# MIC_Speaker.net
KiCad netlist of a schematic drawn in Altium Designer
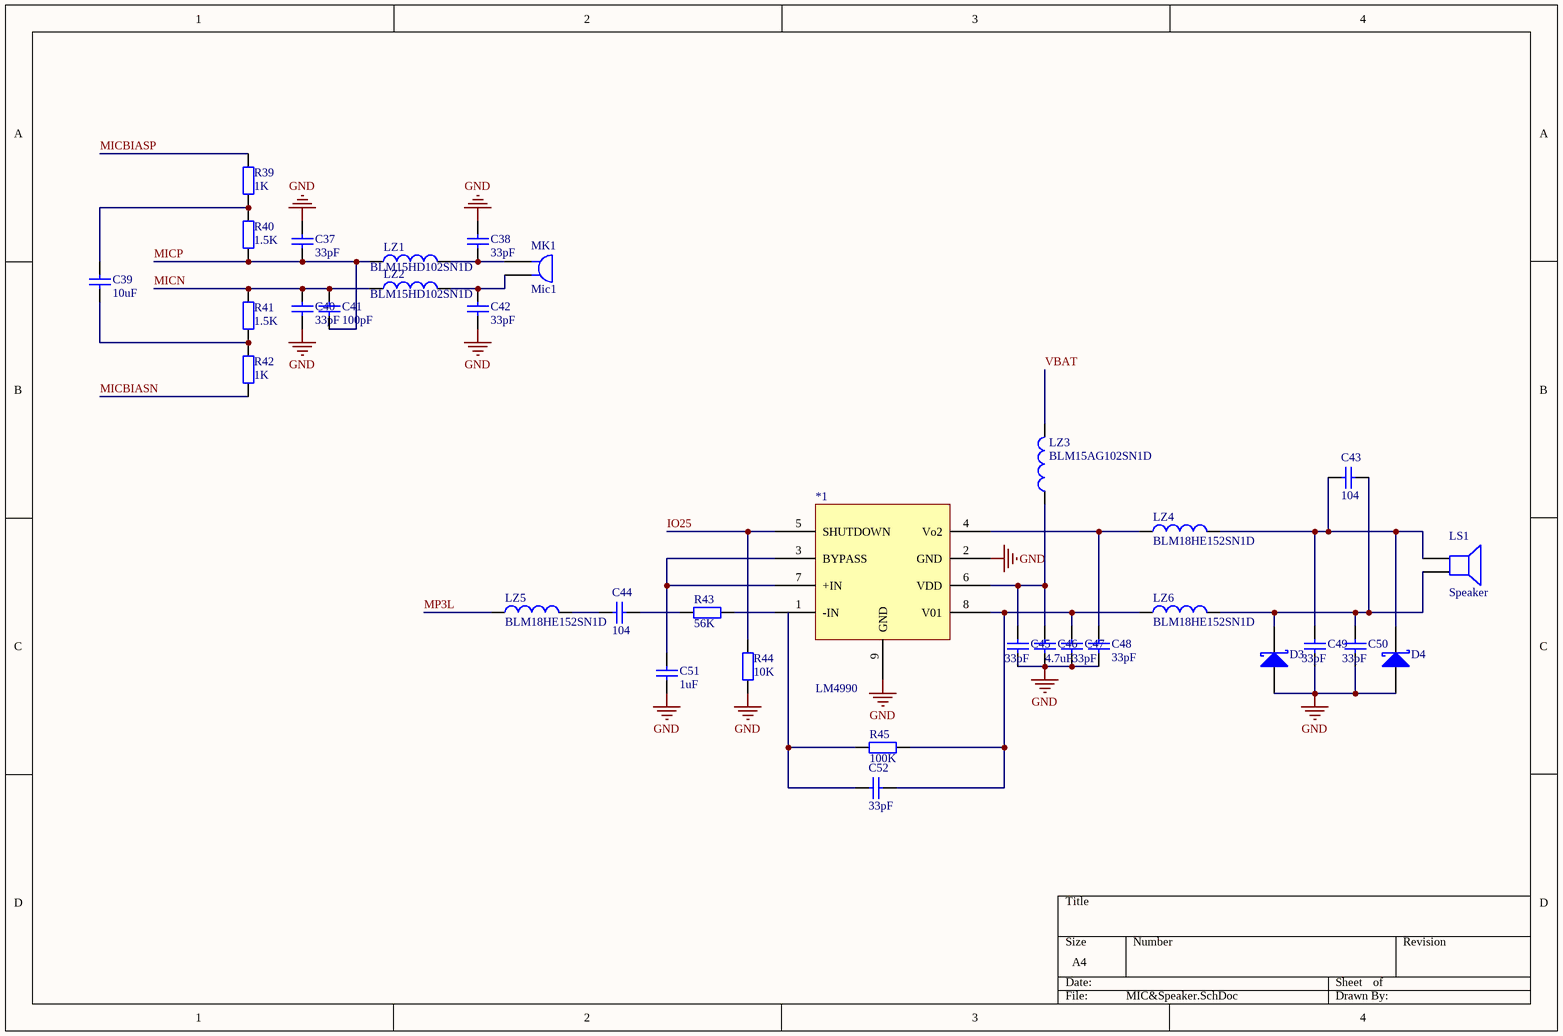
[diagram p0: MIC&Speaker.SchDoc]

(export (version "E")
  (design (tool "Eeschema 10.0.6"))
  (components
    (comp (ref "*1") (value "LM4990") (libsource (lib "*") (part "LM4990")))
    (comp (ref "C37")
      (value "33pF")
      (footprint "1608[0603]")
      (description "Capacitor")
      (fields (field (name "Comment") "Cap") (field (name "PUBLISHER") "Altium Limited"))
      (libsource (lib "common") (part "Cap"))
    )
    (comp (ref "C38")
      (value "33pF")
      (footprint "1608[0603]")
      (description "Capacitor")
      (fields (field (name "Comment") "Cap") (field (name "PUBLISHER") "Altium Limited"))
      (libsource (lib "common") (part "Cap"))
    )
    (comp (ref "C39")
      (value "10uF")
      (footprint "1608[0603]")
      (description "Capacitor")
      (fields (field (name "Comment") "Cap") (field (name "PUBLISHER") "Altium Limited"))
      (libsource (lib "common") (part "Cap"))
    )
    (comp (ref "C40")
      (value "33pF")
      (footprint "1608[0603]")
      (description "Capacitor")
      (fields (field (name "Comment") "Cap") (field (name "PUBLISHER") "Altium Limited"))
      (libsource (lib "common") (part "Cap"))
    )
    (comp (ref "C41")
      (value "100pF")
      (footprint "1608[0603]")
      (description "Capacitor")
      (fields (field (name "Comment") "Cap") (field (name "PUBLISHER") "Altium Limited"))
      (libsource (lib "common") (part "Cap"))
    )
    (comp (ref "C42")
      (value "33pF")
      (footprint "1608[0603]")
      (description "Capacitor")
      (fields (field (name "Comment") "Cap") (field (name "PUBLISHER") "Altium Limited"))
      (libsource (lib "common") (part "Cap"))
    )
    (comp (ref "C43")
      (value "104")
      (footprint "1608[0603]")
      (description "Capacitor")
      (fields (field (name "Comment") "Cap") (field (name "PUBLISHER") "Altium Limited"))
      (libsource (lib "common") (part "Cap"))
    )
    (comp (ref "C44")
      (value "104")
      (footprint "1608[0603]")
      (description "Capacitor")
      (fields (field (name "Comment") "Cap") (field (name "PUBLISHER") "Altium Limited"))
      (libsource (lib "common") (part "Cap"))
    )
    (comp (ref "C45")
      (value "33pF")
      (footprint "1608[0603]")
      (description "Capacitor")
      (fields (field (name "Comment") "Cap") (field (name "PUBLISHER") "Altium Limited"))
      (libsource (lib "common") (part "Cap"))
    )
    (comp (ref "C46")
      (value "4.7uF")
      (footprint "1608[0603]")
      (description "Capacitor")
      (fields (field (name "Comment") "Cap") (field (name "PUBLISHER") "Altium Limited"))
      (libsource (lib "common") (part "Cap"))
    )
    (comp (ref "C47")
      (value "33pF")
      (footprint "1608[0603]")
      (description "Capacitor")
      (fields (field (name "Comment") "Cap") (field (name "PUBLISHER") "Altium Limited"))
      (libsource (lib "common") (part "Cap"))
    )
    (comp (ref "C48")
      (value "33pF")
      (footprint "1608[0603]")
      (description "Capacitor")
      (fields (field (name "Comment") "Cap") (field (name "PUBLISHER") "Altium Limited"))
      (libsource (lib "common") (part "Cap"))
    )
    (comp (ref "C49")
      (value "33pF")
      (footprint "1608[0603]")
      (description "Capacitor")
      (fields (field (name "Comment") "Cap") (field (name "PUBLISHER") "Altium Limited"))
      (libsource (lib "common") (part "Cap"))
    )
    (comp (ref "C50")
      (value "33pF")
      (footprint "1608[0603]")
      (description "Capacitor")
      (fields (field (name "Comment") "Cap") (field (name "PUBLISHER") "Altium Limited"))
      (libsource (lib "common") (part "Cap"))
    )
    (comp (ref "C51")
      (value "1uF")
      (footprint "1608[0603]")
      (description "Capacitor")
      (fields (field (name "Comment") "Cap") (field (name "PUBLISHER") "Altium Limited"))
      (libsource (lib "common") (part "Cap"))
    )
    (comp (ref "C52")
      (value "33pF")
      (footprint "1608[0603]")
      (description "Capacitor")
      (fields (field (name "Comment") "Cap") (field (name "PUBLISHER") "Altium Limited"))
      (libsource (lib "common") (part "Cap"))
    )
    (comp (ref "D3")
      (value "Diode BAT17")
      (footprint "SOT-23")
      (description "Silicon RF Schottky Diode for Mixer Applications in the VHF/UHF Range")
      (fields (field (name "PUBLISHER") "Altium Limited"))
      (libsource (lib "Miscellaneous Devices") (part "Diode BAT17"))
    )
    (comp (ref "D4")
      (value "Diode BAT17")
      (footprint "SOT-23")
      (description "Silicon RF Schottky Diode for Mixer Applications in the VHF/UHF Range")
      (fields (field (name "PUBLISHER") "Altium Limited"))
      (libsource (lib "Miscellaneous Devices") (part "Diode BAT17"))
    )
    (comp (ref "LS1")
      (value "Speaker")
      (footprint "PIN2")
      (description "Loudspeaker")
      (fields (field (name "PUBLISHER") "Altium Limited"))
      (libsource (lib "Miscellaneous Devices") (part "Speaker"))
    )
    (comp (ref "LZ1")
      (value "Inductor")
      (footprint "0402-A")
      (fields (field (name "ALTIUM_UNNAMED_1") "BLM15HD102SN1D") (field (name "PUBLISHER") "Altium Limited"))
      (libsource (lib "Miscellaneous Devices") (part "Inductor"))
    )
    (comp (ref "LZ2")
      (value "Inductor")
      (footprint "0402-A")
      (fields (field (name "ALTIUM_UNNAMED_1") "BLM15HD102SN1D") (field (name "PUBLISHER") "Altium Limited"))
      (libsource (lib "Miscellaneous Devices") (part "Inductor"))
    )
    (comp (ref "LZ3")
      (value "BLM15AG102SN1D")
      (footprint "0402-A")
      (description "Inductor")
      (fields (field (name "PUBLISHER") "Altium Limited"))
      (libsource (lib "Miscellaneous Devices") (part "Inductor"))
    )
    (comp (ref "LZ4")
      (value "BLM18HE152SN1D")
      (footprint "0402-A")
      (description "Inductor")
      (fields (field (name "PUBLISHER") "Altium Limited"))
      (libsource (lib "Miscellaneous Devices") (part "Inductor"))
    )
    (comp (ref "LZ5")
      (value "BLM18HE152SN1D")
      (footprint "0402-A")
      (description "Inductor")
      (fields (field (name "PUBLISHER") "Altium Limited"))
      (libsource (lib "Miscellaneous Devices") (part "Inductor"))
    )
    (comp (ref "LZ6")
      (value "BLM18HE152SN1D")
      (footprint "0402-A")
      (description "Inductor")
      (fields (field (name "PUBLISHER") "Altium Limited"))
      (libsource (lib "Miscellaneous Devices") (part "Inductor"))
    )
    (comp (ref "MK1")
      (value "Mic1")
      (footprint "PIN2")
      (description "Microphone")
      (fields (field (name "PUBLISHER") "Altium Limited"))
      (libsource (lib "Miscellaneous Devices") (part "Mic1"))
    )
    (comp (ref "R39")
      (value "1K")
      (footprint "1608[0603]")
      (description "Resistor")
      (fields (field (name "Comment") "Res") (field (name "PUBLISHER") "Altium Limited"))
      (libsource (lib "") (part "RES_1"))
    )
    (comp (ref "R40")
      (value "1.5K")
      (footprint "1608[0603]")
      (description "Resistor")
      (fields (field (name "Comment") "Res") (field (name "PUBLISHER") "Altium Limited"))
      (libsource (lib "") (part "RES_1"))
    )
    (comp (ref "R41")
      (value "1.5K")
      (footprint "1608[0603]")
      (description "Resistor")
      (fields (field (name "Comment") "Res") (field (name "PUBLISHER") "Altium Limited"))
      (libsource (lib "") (part "RES_1"))
    )
    (comp (ref "R42")
      (value "1K")
      (footprint "1608[0603]")
      (description "Resistor")
      (fields (field (name "Comment") "Res") (field (name "PUBLISHER") "Altium Limited"))
      (libsource (lib "") (part "RES_1"))
    )
    (comp (ref "R43")
      (value "56K")
      (footprint "1608[0603]")
      (description "Resistor")
      (fields (field (name "Comment") "Res") (field (name "PUBLISHER") "Altium Limited"))
      (libsource (lib "common") (part "RES"))
    )
    (comp (ref "R44")
      (value "10K")
      (footprint "1608[0603]")
      (description "Resistor")
      (fields (field (name "Comment") "Res") (field (name "PUBLISHER") "Altium Limited"))
      (libsource (lib "") (part "RES_1"))
    )
    (comp (ref "R45")
      (value "100K")
      (footprint "1608[0603]")
      (description "Resistor")
      (fields (field (name "Comment") "Res") (field (name "PUBLISHER") "Altium Limited"))
      (libsource (lib "common") (part "RES"))
    )
  )
  (nets
    (net (code "1") (name "/IO25") (class "Default")
      (node (ref "*1") (pin "5") (pinfunction "SHUTDOWN_5") (pintype "passive"))
      (node (ref "R44") (pin "2") (pinfunction "2_2") (pintype "passive"))
    )
    (net (code "2") (name "/MICBIASN") (class "Default")
      (node (ref "R42") (pin "1") (pinfunction "1_1") (pintype "passive"))
    )
    (net (code "3") (name "/MICBIASP") (class "Default")
      (node (ref "R39") (pin "2") (pinfunction "2_2") (pintype "passive"))
    )
    (net (code "4") (name "/MICN") (class "Default")
      (node (ref "C40") (pin "2") (pinfunction "2_2") (pintype "passive"))
      (node (ref "C41") (pin "2") (pinfunction "2_2") (pintype "passive"))
      (node (ref "LZ2") (pin "1") (pinfunction "1_1") (pintype "passive"))
      (node (ref "R41") (pin "2") (pinfunction "2_2") (pintype "passive"))
    )
    (net (code "5") (name "/MICP") (class "Default")
      (node (ref "C37") (pin "1") (pinfunction "1_1") (pintype "passive"))
      (node (ref "C41") (pin "1") (pinfunction "1_1") (pintype "passive"))
      (node (ref "LZ1") (pin "1") (pinfunction "1_1") (pintype "passive"))
      (node (ref "R40") (pin "1") (pinfunction "1_1") (pintype "passive"))
    )
    (net (code "6") (name "/MP3L") (class "Default")
      (node (ref "LZ5") (pin "1") (pinfunction "1_1") (pintype "passive"))
    )
    (net (code "7") (name "/VBAT") (class "Default")
      (node (ref "LZ3") (pin "2") (pinfunction "2_2") (pintype "passive"))
    )
    (net (code "8") (name "GND") (class "Default")
      (node (ref "*1") (pin "2") (pinfunction "GND_2") (pintype "passive"))
      (node (ref "*1") (pin "9") (pinfunction "GND_9") (pintype "passive"))
      (node (ref "C37") (pin "2") (pinfunction "2_2") (pintype "passive"))
      (node (ref "C38") (pin "2") (pinfunction "2_2") (pintype "passive"))
      (node (ref "C40") (pin "1") (pinfunction "1_1") (pintype "passive"))
      (node (ref "C42") (pin "1") (pinfunction "1_1") (pintype "passive"))
      (node (ref "C45") (pin "2") (pinfunction "2_2") (pintype "passive"))
      (node (ref "C46") (pin "2") (pinfunction "2_2") (pintype "passive"))
      (node (ref "C47") (pin "2") (pinfunction "2_2") (pintype "passive"))
      (node (ref "C49") (pin "2") (pinfunction "2_2") (pintype "passive"))
      (node (ref "C50") (pin "2") (pinfunction "2_2") (pintype "passive"))
      (node (ref "C51") (pin "2") (pinfunction "2_2") (pintype "passive"))
      (node (ref "D3") (pin "1") (pinfunction "A_1") (pintype "passive"))
      (node (ref "D4") (pin "1") (pinfunction "A_1") (pintype "passive"))
      (node (ref "R44") (pin "1") (pinfunction "1_1") (pintype "passive"))
    )
    (net (code "9") (name "Net-(*1-+IN)") (class "Default")
      (node (ref "*1") (pin "3") (pinfunction "BYPASS_3") (pintype "passive"))
      (node (ref "*1") (pin "7") (pinfunction "+IN_7") (pintype "passive"))
      (node (ref "C51") (pin "1") (pinfunction "1_1") (pintype "passive"))
    )
    (net (code "10") (name "Net-(*1--IN)") (class "Default")
      (node (ref "*1") (pin "1") (pinfunction "-IN_1") (pintype "passive"))
      (node (ref "R43") (pin "1") (pinfunction "1_1") (pintype "passive"))
    )
    (net (code "11") (name "Net-(*1-V01)") (class "Default")
      (node (ref "*1") (pin "8") (pinfunction "V01_8") (pintype "passive"))
      (node (ref "C47") (pin "1") (pinfunction "1_1") (pintype "passive"))
      (node (ref "C52") (pin "1") (pinfunction "1_1") (pintype "passive"))
      (node (ref "LZ6") (pin "1") (pinfunction "1_1") (pintype "passive"))
      (node (ref "R45") (pin "1") (pinfunction "1_1") (pintype "passive"))
    )
    (net (code "12") (name "Net-(*1-VDD)") (class "Default")
      (node (ref "*1") (pin "6") (pinfunction "VDD_6") (pintype "passive"))
      (node (ref "C45") (pin "1") (pinfunction "1_1") (pintype "passive"))
      (node (ref "C46") (pin "1") (pinfunction "1_1") (pintype "passive"))
      (node (ref "LZ3") (pin "1") (pinfunction "1_1") (pintype "passive"))
    )
    (net (code "13") (name "Net-(*1-Vo2)") (class "Default")
      (node (ref "*1") (pin "4") (pinfunction "Vo2_4") (pintype "passive"))
      (node (ref "C48") (pin "1") (pinfunction "1_1") (pintype "passive"))
      (node (ref "LZ4") (pin "1") (pinfunction "1_1") (pintype "passive"))
    )
    (net (code "14") (name "Net-(C38-Pad1)") (class "Default")
      (node (ref "C38") (pin "1") (pinfunction "1_1") (pintype "passive"))
      (node (ref "LZ1") (pin "2") (pinfunction "2_2") (pintype "passive"))
      (node (ref "MK1") (pin "1") (pinfunction "1_1") (pintype "passive"))
    )
    (net (code "15") (name "Net-(C39-Pad1)") (class "Default")
      (node (ref "C39") (pin "1") (pinfunction "1_1") (pintype "passive"))
      (node (ref "R41") (pin "1") (pinfunction "1_1") (pintype "passive"))
      (node (ref "R42") (pin "2") (pinfunction "2_2") (pintype "passive"))
    )
    (net (code "16") (name "Net-(C39-Pad2)") (class "Default")
      (node (ref "C39") (pin "2") (pinfunction "2_2") (pintype "passive"))
      (node (ref "R39") (pin "1") (pinfunction "1_1") (pintype "passive"))
      (node (ref "R40") (pin "2") (pinfunction "2_2") (pintype "passive"))
    )
    (net (code "17") (name "Net-(C42-Pad2)") (class "Default")
      (node (ref "C42") (pin "2") (pinfunction "2_2") (pintype "passive"))
      (node (ref "LZ2") (pin "2") (pinfunction "2_2") (pintype "passive"))
      (node (ref "MK1") (pin "2") (pinfunction "2_2") (pintype "passive"))
    )
    (net (code "18") (name "Net-(C44-Pad1)") (class "Default")
      (node (ref "C44") (pin "1") (pinfunction "1_1") (pintype "passive"))
      (node (ref "R43") (pin "2") (pinfunction "2_2") (pintype "passive"))
    )
    (net (code "19") (name "Net-(C44-Pad2)") (class "Default")
      (node (ref "C44") (pin "2") (pinfunction "2_2") (pintype "passive"))
      (node (ref "LZ5") (pin "2") (pinfunction "2_2") (pintype "passive"))
    )
    (net (code "20") (name "Net-(C52-Pad2)") (class "Default")
      (node (ref "C52") (pin "2") (pinfunction "2_2") (pintype "passive"))
      (node (ref "R45") (pin "2") (pinfunction "2_2") (pintype "passive"))
    )
    (net (code "21") (name "Net-(D3-K)") (class "Default")
      (node (ref "C43") (pin "1") (pinfunction "1_1") (pintype "passive"))
      (node (ref "C50") (pin "1") (pinfunction "1_1") (pintype "passive"))
      (node (ref "D3") (pin "3") (pinfunction "K_3") (pintype "passive"))
      (node (ref "LS1") (pin "2") (pinfunction "2_2") (pintype "passive"))
      (node (ref "LZ6") (pin "2") (pinfunction "2_2") (pintype "passive"))
    )
    (net (code "22") (name "Net-(D4-K)") (class "Default")
      (node (ref "C43") (pin "2") (pinfunction "2_2") (pintype "passive"))
      (node (ref "C49") (pin "1") (pinfunction "1_1") (pintype "passive"))
      (node (ref "D4") (pin "3") (pinfunction "K_3") (pintype "passive"))
      (node (ref "LS1") (pin "1") (pinfunction "1_1") (pintype "passive"))
      (node (ref "LZ4") (pin "2") (pinfunction "2_2") (pintype "passive"))
    )
    (net (code "23") (name "unconnected-(C48-Pad2)") (class "Default")
      (node (ref "C48") (pin "2") (pinfunction "2_2") (pintype "passive"))
    )
  )
)
